# Magnetometer.net
KiCad netlist of a schematic drawn in Altium Designer
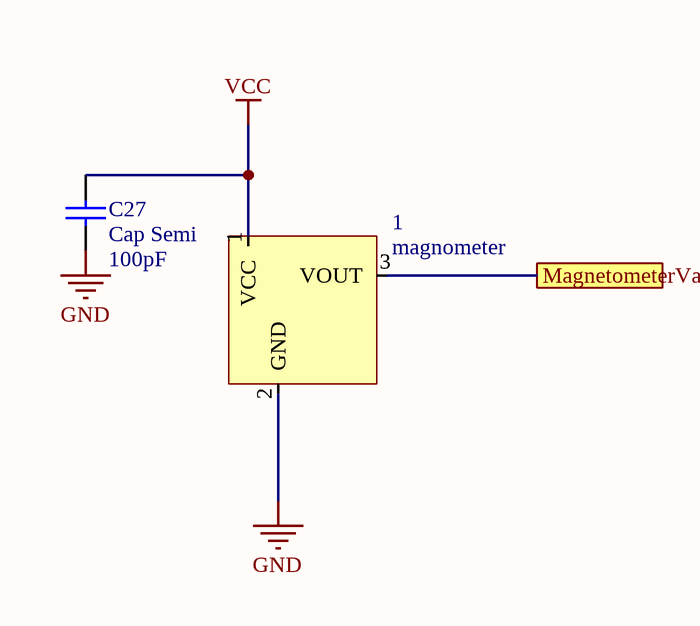
[diagram p0: Magnetometer.SchDoc]

(export (version "E")
  (design (tool "Eeschema 10.0.6"))
  (components
    (comp (ref "1")
      (value "magnometer")
      (footprint "SIP-3")
      (libsource (lib "HGCDLibrary") (part "magnometer"))
    )
    (comp (ref "C27")
      (value "Cap Semi")
      (footprint "C1206")
      (description "Capacitor (Semiconductor SIM Model)")
      (fields (field (name "ALTIUM_VALUE") "100pF") (field (name "PUBLISHER") "Altium Limited"))
      (libsource (lib "Miscellaneous Devices") (part "Cap Semi"))
    )
  )
  (nets
    (net (code "1") (name "/MagnetometerVal") (class "Default")
      (node (ref "1") (pin "3") (pinfunction "VOUT_3") (pintype "output"))
    )
    (net (code "2") (name "GND") (class "Default")
      (node (ref "1") (pin "2") (pinfunction "GND_2") (pintype "power_in"))
      (node (ref "C27") (pin "1") (pinfunction "1_1") (pintype "passive"))
    )
    (net (code "3") (name "VCC") (class "Default")
      (node (ref "1") (pin "1") (pinfunction "VCC_1") (pintype "power_in"))
      (node (ref "C27") (pin "2") (pinfunction "2_2") (pintype "passive"))
    )
  )
)
